# ToF_Board.net
KiCad netlist of a schematic drawn in Altium Designer
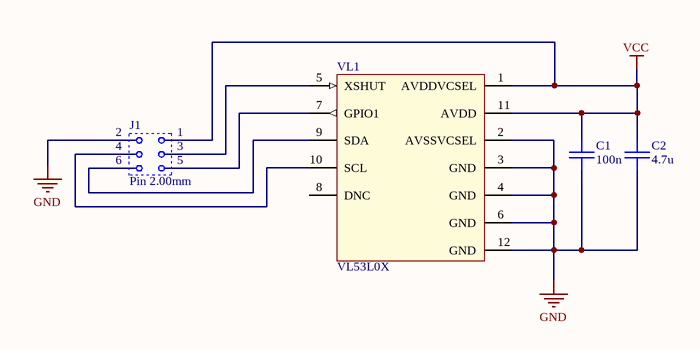
[diagram p0: ToF_Board.SchDoc]

(export (version "E")
  (design (tool "Eeschema 10.0.6"))
  (components
    (comp (ref "C1")
      (value "100n")
      (footprint "Other-Discrete:0603")
      (description "Ceramic Capacitor")
      (libsource (lib "Disc-Other") (part "C_CER"))
    )
    (comp (ref "C2")
      (value "4.7u")
      (footprint "Other-Discrete:0603")
      (description "Ceramic Capacitor")
      (libsource (lib "Disc-Other") (part "C_CER"))
    )
    (comp (ref "J1")
      (value "Pin 2.00mm")
      (footprint "2mmEdgePCB6Pin")
      (libsource (lib "Connectors") (part "Goldpin 2.00 pin 2x3"))
    )
    (comp (ref "VL1")
      (value "VL53L0X")
      (footprint "LGA12")
      (description "Time-of-Flight ranging and gesture detection sensor")
      (libsource (lib "rys_component_lib") (part "VL53L0X ToF"))
    )
  )
  (nets
    (net (code "1") (name "GND") (class "Default")
      (node (ref "C1") (pin "2") (pinfunction "2_2") (pintype "passive"))
      (node (ref "C2") (pin "2") (pinfunction "2_2") (pintype "passive"))
      (node (ref "J1") (pin "2") (pintype "passive"))
      (node (ref "VL1") (pin "12") (pinfunction "GND_12") (pintype "passive"))
      (node (ref "VL1") (pin "2") (pinfunction "AVSSVCSEL_2") (pintype "passive"))
      (node (ref "VL1") (pin "3") (pinfunction "GND_3") (pintype "passive"))
      (node (ref "VL1") (pin "4") (pinfunction "GND_4") (pintype "passive"))
      (node (ref "VL1") (pin "6") (pinfunction "GND_6") (pintype "passive"))
    )
    (net (code "2") (name "Net-(VL1-GPIO1)") (class "Default")
      (node (ref "J1") (pin "5") (pintype "passive"))
      (node (ref "VL1") (pin "7") (pinfunction "GPIO1_7") (pintype "output"))
    )
    (net (code "3") (name "Net-(VL1-SCL)") (class "Default")
      (node (ref "J1") (pin "4") (pintype "passive"))
      (node (ref "VL1") (pin "10") (pinfunction "SCL_10") (pintype "passive"))
    )
    (net (code "4") (name "Net-(VL1-SDA)") (class "Default")
      (node (ref "J1") (pin "6") (pintype "passive"))
      (node (ref "VL1") (pin "9") (pinfunction "SDA_9") (pintype "passive"))
    )
    (net (code "5") (name "Net-(VL1-XSHUT)") (class "Default")
      (node (ref "J1") (pin "3") (pintype "passive"))
      (node (ref "VL1") (pin "5") (pinfunction "XSHUT_5") (pintype "input"))
    )
    (net (code "6") (name "VCC") (class "Default")
      (node (ref "C1") (pin "1") (pinfunction "1_1") (pintype "passive"))
      (node (ref "C2") (pin "1") (pinfunction "1_1") (pintype "passive"))
      (node (ref "J1") (pin "1") (pintype "passive"))
      (node (ref "VL1") (pin "1") (pinfunction "AVDDVCSEL_1") (pintype "passive"))
      (node (ref "VL1") (pin "11") (pinfunction "AVDD_11") (pintype "passive"))
    )
    (net (code "7") (name "unconnected-(VL1-DNC-Pad8)") (class "Default")
      (node (ref "VL1") (pin "8") (pinfunction "DNC_8") (pintype "passive"))
    )
  )
)
